# ESP8266_STANDLONE_2021-05-12.net
KiCad netlist of a schematic drawn in EasyEDA
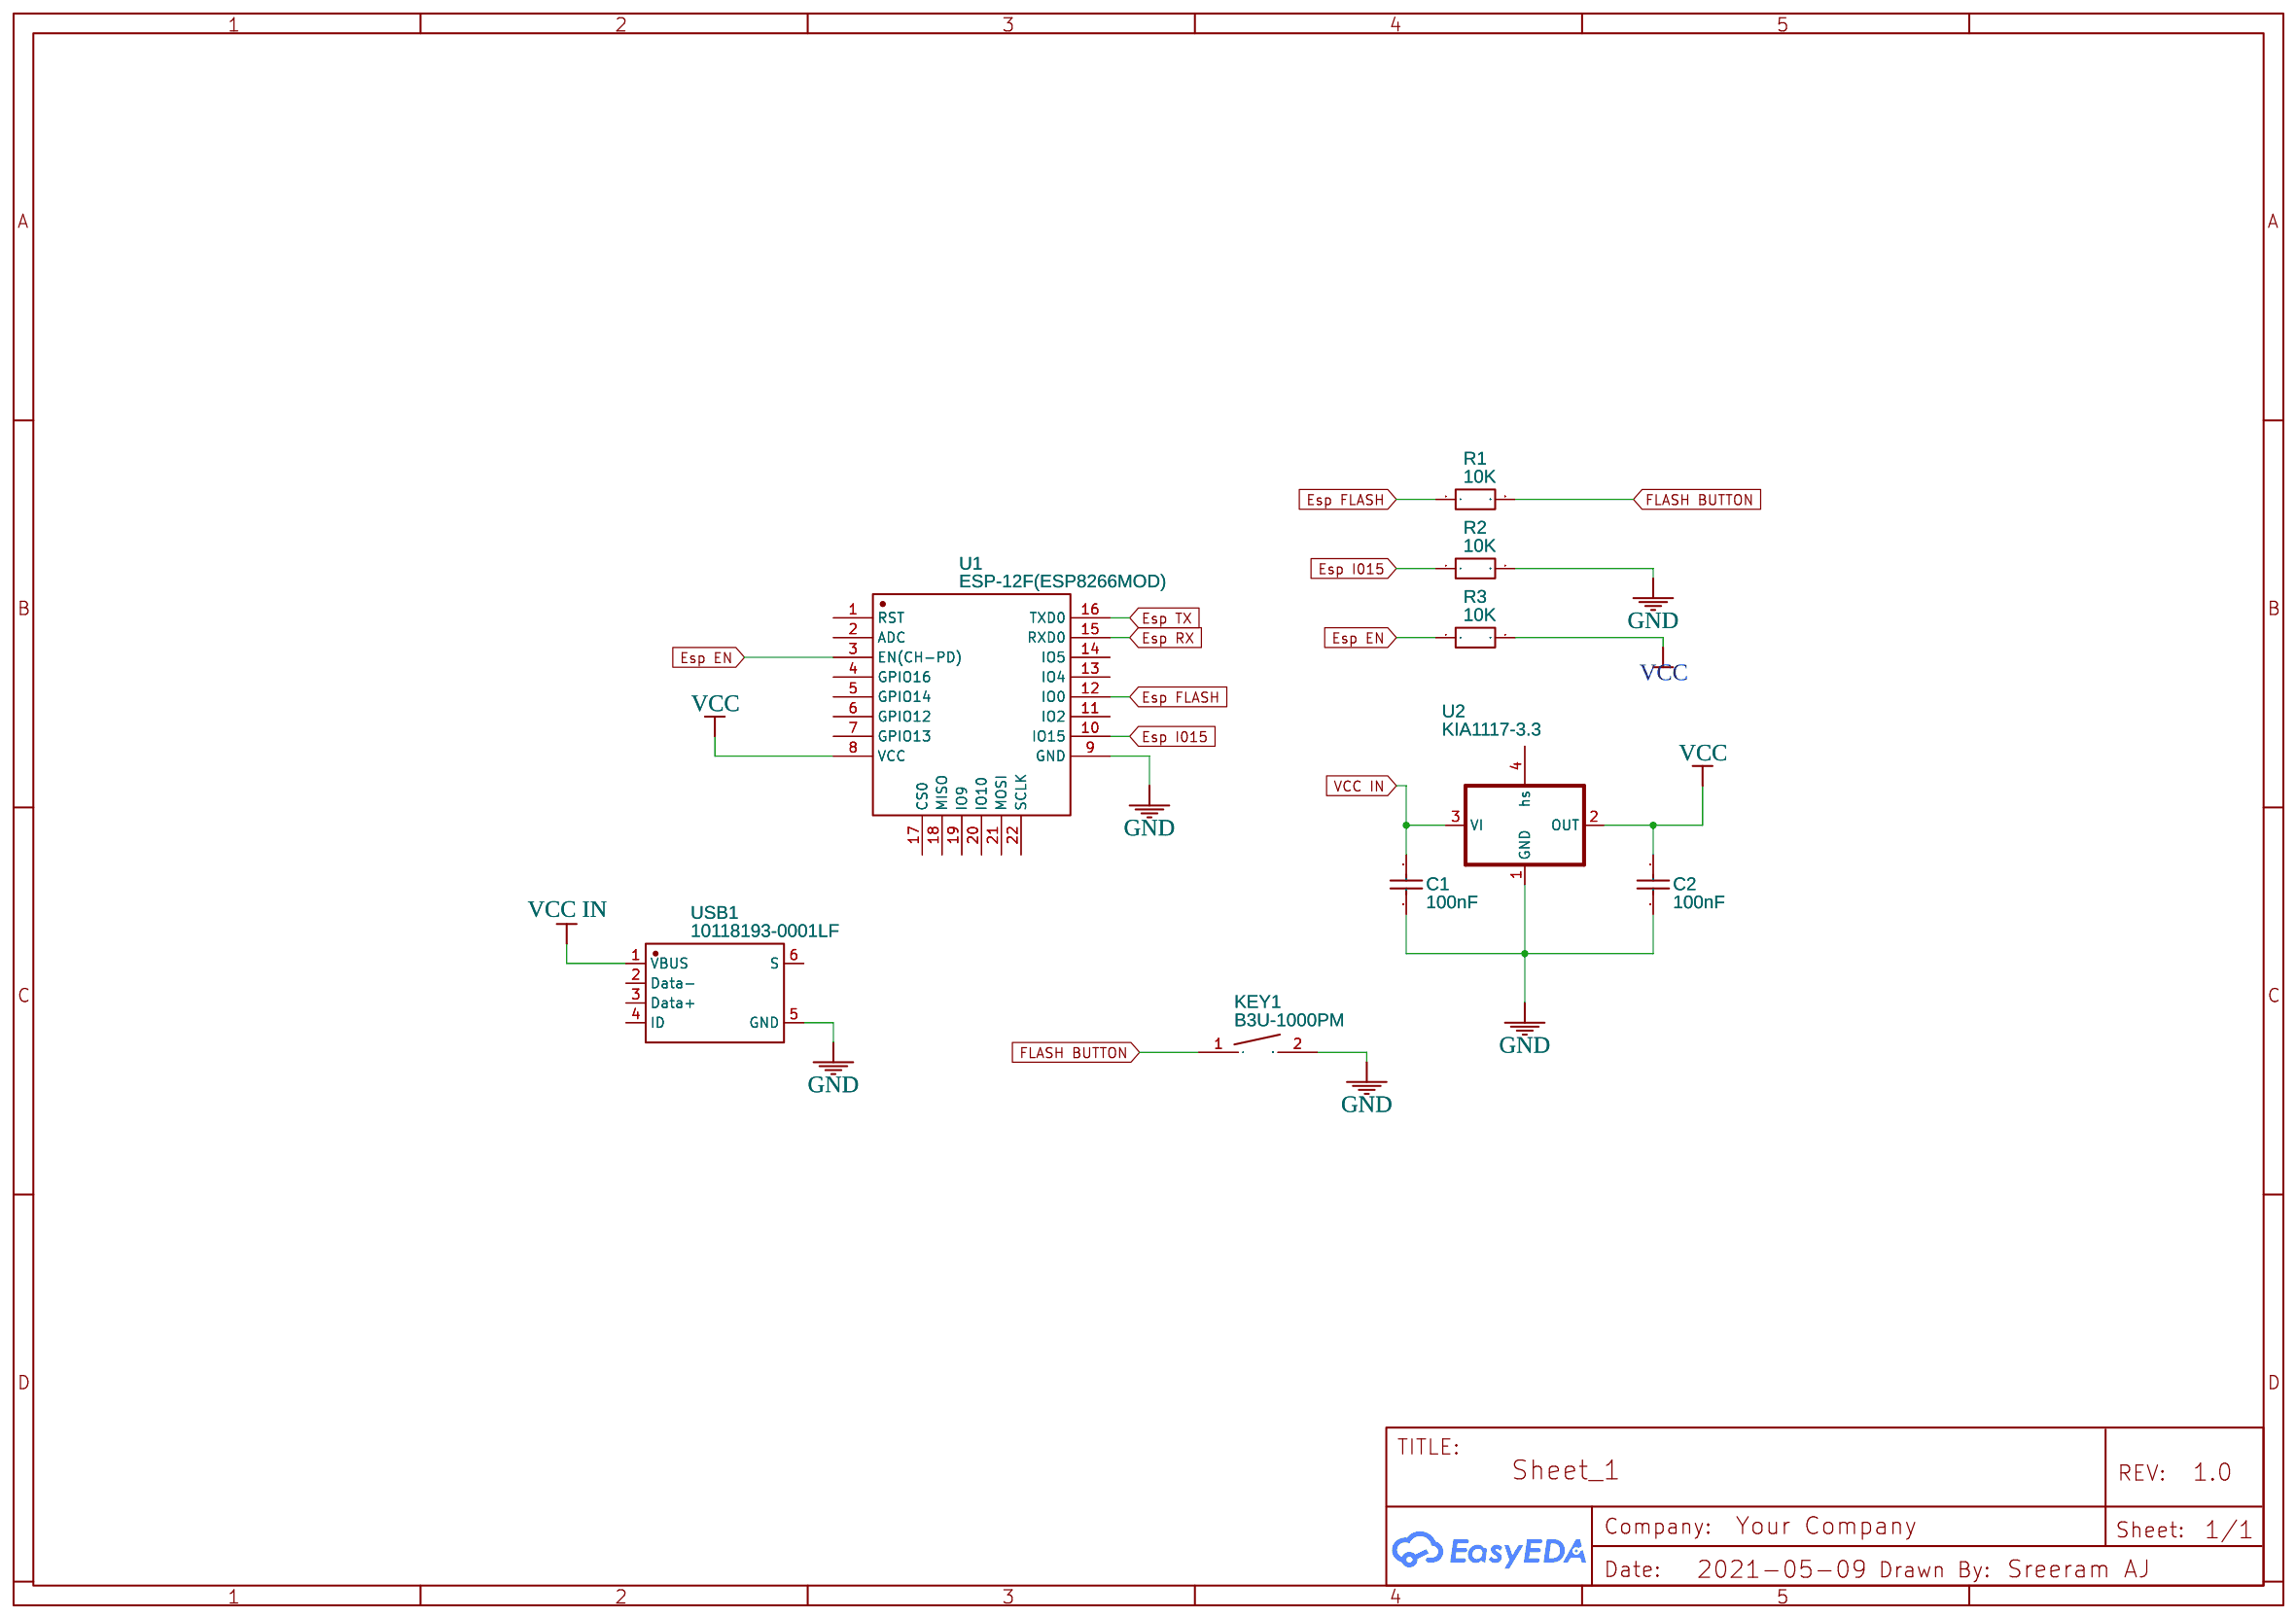
[diagram p0: schematic sheet]

(export (version "E")
  (design (tool "Eeschema 10.0.6"))
  (components
    (comp (ref "C1")
      (value "100nF")
      (fields
        (field (name "BOM_Manufacturer Part") "0.1UF(104) +-20% 63v")
        (field (name "BOM_Supplier Part") "C19355")
      )
      (libsource (lib "") (part "100nF"))
    )
    (comp (ref "C2")
      (value "100nF")
      (fields
        (field (name "BOM_Manufacturer Part") "0.1UF(104) +-20% 63v")
        (field (name "BOM_Supplier Part") "C19355")
      )
      (libsource (lib "") (part "100nF"))
    )
    (comp (ref "KEY1")
      (value "B3U-1000PM")
      (fields (field (name "BOM_Supplier Part") "C271754"))
      (libsource (lib "") (part "B3U-1000PM"))
    )
    (comp (ref "R1")
      (value "10K")
      (fields
        (field (name "BOM_Manufacturer Part") "RN 3WS 10K F T/B A1")
        (field (name "BOM_Supplier Part") "C433569")
      )
      (libsource (lib "") (part "RN 3WS 10K F T/B A1"))
    )
    (comp (ref "R2")
      (value "10K")
      (fields
        (field (name "BOM_Manufacturer Part") "RN 3WS 10K F T/B A1")
        (field (name "BOM_Supplier Part") "C433569")
      )
      (libsource (lib "") (part "RN 3WS 10K F T/B A1"))
    )
    (comp (ref "R3")
      (value "10K")
      (fields
        (field (name "BOM_Manufacturer Part") "RN 3WS 10K F T/B A1")
        (field (name "BOM_Supplier Part") "C433569")
      )
      (libsource (lib "") (part "RN 3WS 10K F T/B A1"))
    )
    (comp (ref "U1")
      (value "ESP-12F(ESP8266MOD)")
      (fields (field (name "BOM_Supplier Part") "C82891"))
      (libsource (lib "") (part "ESP-12F(ESP8266MOD)"))
    )
    (comp (ref "U2")
      (value "KIA1117-3.3")
      (fields (field (name "BOM_Supplier Part") "C116069"))
      (libsource (lib "") (part "KIA1117-3.3"))
    )
    (comp (ref "USB1")
      (value "10118193-0001LF")
      (fields (field (name "BOM_Supplier Part") "C132562"))
      (libsource (lib "") (part "10118193-0001LF"))
    )
  )
  (nets
    (net (code "1") (name "Esp EN") (class "Default")
      (node (ref "R3") (pin "1") (pinfunction "1_1") (pintype "unspecified"))
      (node (ref "U1") (pin "3") (pinfunction "EN(CH-PD)_3") (pintype "unspecified"))
    )
    (net (code "2") (name "Esp FLASH") (class "Default")
      (node (ref "R1") (pin "1") (pinfunction "1_1") (pintype "unspecified"))
      (node (ref "U1") (pin "12") (pinfunction "IO0_12") (pintype "unspecified"))
    )
    (net (code "3") (name "Esp I015") (class "Default")
      (node (ref "R2") (pin "1") (pinfunction "1_1") (pintype "unspecified"))
      (node (ref "U1") (pin "10") (pinfunction "IO15_10") (pintype "unspecified"))
    )
    (net (code "4") (name "Esp RX") (class "Default")
      (node (ref "U1") (pin "15") (pinfunction "RXD0_15") (pintype "unspecified"))
    )
    (net (code "5") (name "Esp TX") (class "Default")
      (node (ref "U1") (pin "16") (pinfunction "TXD0_16") (pintype "unspecified"))
    )
    (net (code "6") (name "FLASH BUTTON") (class "Default")
      (node (ref "KEY1") (pin "1") (pinfunction "1_1") (pintype "input"))
      (node (ref "R1") (pin "2") (pinfunction "2_2") (pintype "unspecified"))
    )
    (net (code "7") (name "GND") (class "Default")
      (node (ref "C1") (pin "1") (pinfunction "1_1") (pintype "input"))
      (node (ref "C2") (pin "1") (pinfunction "1_1") (pintype "input"))
      (node (ref "KEY1") (pin "2") (pinfunction "2_2") (pintype "input"))
      (node (ref "R2") (pin "2") (pinfunction "2_2") (pintype "unspecified"))
      (node (ref "U1") (pin "9") (pinfunction "GND_9") (pintype "unspecified"))
      (node (ref "U2") (pin "1") (pinfunction "GND_1") (pintype "unspecified"))
      (node (ref "USB1") (pin "5") (pinfunction "GND_5") (pintype "unspecified"))
    )
    (net (code "8") (name "VCC") (class "Default")
      (node (ref "C2") (pin "2") (pinfunction "2_2") (pintype "input"))
      (node (ref "R3") (pin "2") (pinfunction "2_2") (pintype "unspecified"))
      (node (ref "U1") (pin "8") (pinfunction "VCC_8") (pintype "unspecified"))
      (node (ref "U2") (pin "2") (pinfunction "OUT_2") (pintype "unspecified"))
    )
    (net (code "9") (name "VCC IN") (class "Default")
      (node (ref "C1") (pin "2") (pinfunction "2_2") (pintype "input"))
      (node (ref "U2") (pin "3") (pinfunction "VI_3") (pintype "input"))
      (node (ref "USB1") (pin "1") (pinfunction "VBUS_1") (pintype "unspecified"))
    )
    (net (code "10") (name "unconnected-(U1-ADC-Pad2)") (class "Default")
      (node (ref "U1") (pin "2") (pinfunction "ADC_2") (pintype "unspecified"))
    )
    (net (code "11") (name "unconnected-(U1-CS0-Pad17)") (class "Default")
      (node (ref "U1") (pin "17") (pinfunction "CS0_17") (pintype "unspecified"))
    )
    (net (code "12") (name "unconnected-(U1-GPIO12-Pad6)") (class "Default")
      (node (ref "U1") (pin "6") (pinfunction "GPIO12_6") (pintype "unspecified"))
    )
    (net (code "13") (name "unconnected-(U1-GPIO13-Pad7)") (class "Default")
      (node (ref "U1") (pin "7") (pinfunction "GPIO13_7") (pintype "unspecified"))
    )
    (net (code "14") (name "unconnected-(U1-GPIO14-Pad5)") (class "Default")
      (node (ref "U1") (pin "5") (pinfunction "GPIO14_5") (pintype "unspecified"))
    )
    (net (code "15") (name "unconnected-(U1-GPIO16-Pad4)") (class "Default")
      (node (ref "U1") (pin "4") (pinfunction "GPIO16_4") (pintype "unspecified"))
    )
    (net (code "16") (name "unconnected-(U1-IO2-Pad11)") (class "Default")
      (node (ref "U1") (pin "11") (pinfunction "IO2_11") (pintype "unspecified"))
    )
    (net (code "17") (name "unconnected-(U1-IO4-Pad13)") (class "Default")
      (node (ref "U1") (pin "13") (pinfunction "IO4_13") (pintype "unspecified"))
    )
    (net (code "18") (name "unconnected-(U1-IO5-Pad14)") (class "Default")
      (node (ref "U1") (pin "14") (pinfunction "IO5_14") (pintype "unspecified"))
    )
    (net (code "19") (name "unconnected-(U1-IO9-Pad19)") (class "Default")
      (node (ref "U1") (pin "19") (pinfunction "IO9_19") (pintype "unspecified"))
    )
    (net (code "20") (name "unconnected-(U1-IO10-Pad20)") (class "Default")
      (node (ref "U1") (pin "20") (pinfunction "IO10_20") (pintype "unspecified"))
    )
    (net (code "21") (name "unconnected-(U1-MISO-Pad18)") (class "Default")
      (node (ref "U1") (pin "18") (pinfunction "MISO_18") (pintype "unspecified"))
    )
    (net (code "22") (name "unconnected-(U1-MOSI-Pad21)") (class "Default")
      (node (ref "U1") (pin "21") (pinfunction "MOSI_21") (pintype "unspecified"))
    )
    (net (code "23") (name "unconnected-(U1-RST-Pad1)") (class "Default")
      (node (ref "U1") (pin "1") (pinfunction "RST_1") (pintype "unspecified"))
    )
    (net (code "24") (name "unconnected-(U1-SCLK-Pad22)") (class "Default")
      (node (ref "U1") (pin "22") (pinfunction "SCLK_22") (pintype "unspecified"))
    )
    (net (code "25") (name "unconnected-(U2-hs-Pad4)") (class "Default")
      (node (ref "U2") (pin "4") (pinfunction "hs_4") (pintype "unspecified"))
    )
    (net (code "26") (name "unconnected-(USB1-Data+-Pad3)") (class "Default")
      (node (ref "USB1") (pin "3") (pinfunction "Data+_3") (pintype "unspecified"))
    )
    (net (code "27") (name "unconnected-(USB1-Data--Pad2)") (class "Default")
      (node (ref "USB1") (pin "2") (pinfunction "Data-_2") (pintype "unspecified"))
    )
    (net (code "28") (name "unconnected-(USB1-ID-Pad4)") (class "Default")
      (node (ref "USB1") (pin "4") (pinfunction "ID_4") (pintype "unspecified"))
    )
    (net (code "29") (name "unconnected-(USB1-S-Pad6)") (class "Default")
      (node (ref "USB1") (pin "6") (pinfunction "S_6") (pintype "unspecified"))
    )
  )
)
